# rs485.net
KiCad netlist of a schematic drawn in EAGLE
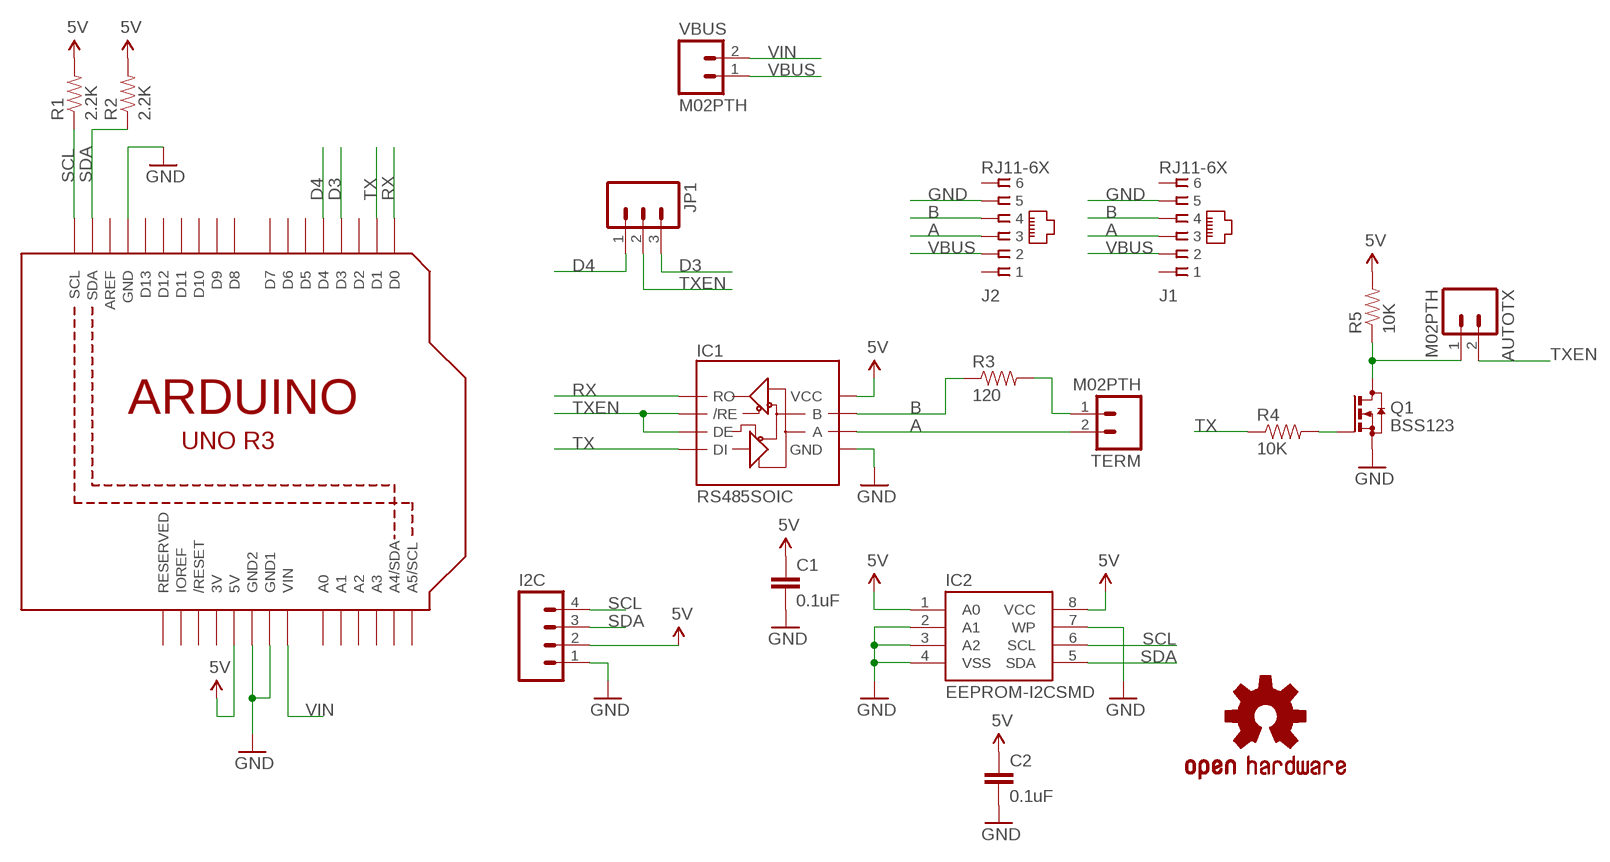
[diagram p0: schematic, sheet 1]

(export (version "E")
  (design (tool "Eeschema 10.0.6"))
  (components
    (comp (ref "AUTOTX")
      (value "M02PTH")
      (footprint "eagle-import:1X02")
      (libsource (lib "eagle-import") (part "M02PTH"))
    )
    (comp (ref "C1")
      (value "0.1uF")
      (footprint "eagle-import:0603-CAP")
      (libsource (lib "eagle-import") (part "CAP0603-CAP"))
    )
    (comp (ref "C2")
      (value "0.1uF")
      (footprint "eagle-import:0603-CAP")
      (libsource (lib "eagle-import") (part "CAP0603-CAP"))
    )
    (comp (ref "I2C")
      (value "M04PTH")
      (footprint "eagle-import:1X04")
      (libsource (lib "eagle-import") (part "M04PTH"))
    )
    (comp (ref "IC1")
      (value "RS485SOIC")
      (footprint "eagle-import:SO08")
      (libsource (lib "eagle-import") (part "RS485SOIC"))
    )
    (comp (ref "IC2")
      (value "EEPROM-I2CSMD")
      (footprint "eagle-import:SO08")
      (libsource (lib "eagle-import") (part "EEPROM-I2CSMD"))
    )
    (comp (ref "J1")
      (value "RJ11-6X")
      (footprint "eagle-import:RJ11-NO_SHIELD")
      (libsource (lib "eagle-import") (part "RJ11-6X"))
    )
    (comp (ref "J2")
      (value "RJ11-6X")
      (footprint "eagle-import:RJ11-NO_SHIELD")
      (libsource (lib "eagle-import") (part "RJ11-6X"))
    )
    (comp (ref "JP1")
      (value "M03PTH")
      (footprint "eagle-import:1X03")
      (libsource (lib "eagle-import") (part "M03PTH"))
    )
    (comp (ref "LOGO1")
      (value "OSHW-LOGOL")
      (footprint "eagle-import:OSHW-LOGO-L")
      (libsource (lib "eagle-import") (part "OSHW-LOGOL"))
    )
    (comp (ref "Q1")
      (value "BSS123")
      (footprint "eagle-import:SOT23")
      (libsource (lib "eagle-import") (part "BSS123"))
    )
    (comp (ref "R1")
      (value "2.2K")
      (footprint "eagle-import:0603-RES")
      (libsource (lib "eagle-import") (part "RESISTOR0603-RES"))
    )
    (comp (ref "R2")
      (value "2.2K")
      (footprint "eagle-import:0603-RES")
      (libsource (lib "eagle-import") (part "RESISTOR0603-RES"))
    )
    (comp (ref "R3")
      (value "120")
      (footprint "eagle-import:0603-RES")
      (libsource (lib "eagle-import") (part "RESISTOR0603-RES"))
    )
    (comp (ref "R4")
      (value "10K")
      (footprint "eagle-import:0603-RES")
      (libsource (lib "eagle-import") (part "RESISTOR0603-RES"))
    )
    (comp (ref "R5")
      (value "10K")
      (footprint "eagle-import:0603-RES")
      (libsource (lib "eagle-import") (part "RESISTOR0603-RES"))
    )
    (comp (ref "TERM")
      (value "M02PTH")
      (footprint "eagle-import:1X02")
      (libsource (lib "eagle-import") (part "M02PTH"))
    )
    (comp (ref "U1")
      (value "ARDUINOR3-JUSTPINS")
      (footprint "eagle-import:ARDUINOR3")
      (libsource (lib "eagle-import") (part "ARDUINOR3-JUSTPINS"))
    )
    (comp (ref "VBUS")
      (value "M02PTH")
      (footprint "eagle-import:1X02")
      (libsource (lib "eagle-import") (part "M02PTH"))
    )
  )
  (nets
    (net (code "1") (name "/3V") (class "Default")
      (node (ref "U1") (pin "3V") (pinfunction "3V_3V") (pintype "power_in"))
    )
    (net (code "2") (name "/A") (class "Default")
      (node (ref "IC1") (pin "6") (pinfunction "A_6") (pintype "bidirectional"))
      (node (ref "J1") (pin "3") (pinfunction "3_3") (pintype "passive"))
      (node (ref "J2") (pin "3") (pinfunction "3_3") (pintype "passive"))
      (node (ref "TERM") (pin "2") (pinfunction "2_2") (pintype "passive"))
    )
    (net (code "3") (name "/B") (class "Default")
      (node (ref "IC1") (pin "7") (pinfunction "B_7") (pintype "bidirectional"))
      (node (ref "J1") (pin "4") (pinfunction "4_4") (pintype "passive"))
      (node (ref "J2") (pin "4") (pinfunction "4_4") (pintype "passive"))
      (node (ref "R3") (pin "1") (pinfunction "1_1") (pintype "passive"))
    )
    (net (code "4") (name "/D3") (class "Default")
      (node (ref "JP1") (pin "3") (pinfunction "3_3") (pintype "passive"))
      (node (ref "U1") (pin "D3") (pinfunction "D3_D3") (pintype "bidirectional"))
    )
    (net (code "5") (name "/D4") (class "Default")
      (node (ref "JP1") (pin "1") (pinfunction "1_1") (pintype "passive"))
      (node (ref "U1") (pin "D4") (pinfunction "D4_D4") (pintype "bidirectional"))
    )
    (net (code "6") (name "/RX") (class "Default")
      (node (ref "IC1") (pin "1") (pinfunction "RO_1") (pintype "bidirectional"))
      (node (ref "U1") (pin "D0") (pinfunction "D0_D0") (pintype "bidirectional"))
    )
    (net (code "7") (name "/SCL") (class "Default")
      (node (ref "I2C") (pin "4") (pinfunction "4_4") (pintype "passive"))
      (node (ref "IC2") (pin "6") (pinfunction "SCL_6") (pintype "bidirectional"))
      (node (ref "R1") (pin "1") (pinfunction "1_1") (pintype "passive"))
      (node (ref "U1") (pin "SCL") (pinfunction "SCL_SCL") (pintype "bidirectional"))
    )
    (net (code "8") (name "/SDA") (class "Default")
      (node (ref "I2C") (pin "3") (pinfunction "3_3") (pintype "passive"))
      (node (ref "IC2") (pin "5") (pinfunction "SDA_5") (pintype "bidirectional"))
      (node (ref "R2") (pin "1") (pinfunction "1_1") (pintype "passive"))
      (node (ref "U1") (pin "SDA") (pinfunction "SDA_SDA") (pintype "bidirectional"))
    )
    (net (code "9") (name "/TX") (class "Default")
      (node (ref "IC1") (pin "4") (pinfunction "DI_4") (pintype "bidirectional"))
      (node (ref "R4") (pin "1") (pinfunction "1_1") (pintype "passive"))
      (node (ref "U1") (pin "D1") (pinfunction "D1_D1") (pintype "bidirectional"))
    )
    (net (code "10") (name "/TXEN") (class "Default")
      (node (ref "AUTOTX") (pin "2") (pinfunction "2_2") (pintype "passive"))
      (node (ref "IC1") (pin "2") (pinfunction "/RE_2") (pintype "bidirectional"))
      (node (ref "IC1") (pin "3") (pinfunction "DE_3") (pintype "bidirectional"))
      (node (ref "JP1") (pin "2") (pinfunction "2_2") (pintype "passive"))
    )
    (net (code "11") (name "/VBUS") (class "Default")
      (node (ref "J1") (pin "2") (pinfunction "2_2") (pintype "passive"))
      (node (ref "J2") (pin "2") (pinfunction "2_2") (pintype "passive"))
      (node (ref "VBUS") (pin "1") (pinfunction "1_1") (pintype "passive"))
    )
    (net (code "12") (name "/VIN") (class "Default")
      (node (ref "U1") (pin "VIN") (pinfunction "VIN_VIN") (pintype "power_in"))
      (node (ref "VBUS") (pin "2") (pinfunction "2_2") (pintype "passive"))
    )
    (net (code "13") (name "5V") (class "Default")
      (node (ref "C1") (pin "1") (pinfunction "1_1") (pintype "passive"))
      (node (ref "C2") (pin "1") (pinfunction "1_1") (pintype "passive"))
      (node (ref "I2C") (pin "2") (pinfunction "2_2") (pintype "passive"))
      (node (ref "IC1") (pin "8") (pinfunction "VCC_8") (pintype "bidirectional"))
      (node (ref "IC2") (pin "1") (pinfunction "A0_1") (pintype "bidirectional"))
      (node (ref "IC2") (pin "8") (pinfunction "VCC_8") (pintype "power_in"))
      (node (ref "R1") (pin "2") (pinfunction "2_2") (pintype "passive"))
      (node (ref "R2") (pin "2") (pinfunction "2_2") (pintype "passive"))
      (node (ref "R5") (pin "2") (pinfunction "2_2") (pintype "passive"))
      (node (ref "U1") (pin "5V") (pinfunction "5V_5V") (pintype "power_in"))
    )
    (net (code "14") (name "GND") (class "Default")
      (node (ref "C1") (pin "2") (pinfunction "2_2") (pintype "passive"))
      (node (ref "C2") (pin "2") (pinfunction "2_2") (pintype "passive"))
      (node (ref "I2C") (pin "1") (pinfunction "1_1") (pintype "passive"))
      (node (ref "IC1") (pin "5") (pinfunction "GND_5") (pintype "bidirectional"))
      (node (ref "IC2") (pin "2") (pinfunction "A1_2") (pintype "bidirectional"))
      (node (ref "IC2") (pin "3") (pinfunction "A2_3") (pintype "bidirectional"))
      (node (ref "IC2") (pin "4") (pinfunction "VSS_4") (pintype "power_in"))
      (node (ref "IC2") (pin "7") (pinfunction "WP_7") (pintype "bidirectional"))
      (node (ref "J1") (pin "5") (pinfunction "5_5") (pintype "passive"))
      (node (ref "J2") (pin "5") (pinfunction "5_5") (pintype "passive"))
      (node (ref "Q1") (pin "2") (pinfunction "S_2") (pintype "passive"))
      (node (ref "U1") (pin "GND") (pinfunction "GND_GND") (pintype "power_in"))
      (node (ref "U1") (pin "GND1") (pinfunction "GND1_GND1") (pintype "power_in"))
      (node (ref "U1") (pin "GND2") (pinfunction "GND2_GND2") (pintype "power_in"))
    )
    (net (code "15") (name "Net-(Q1-D)") (class "Default")
      (node (ref "AUTOTX") (pin "1") (pinfunction "1_1") (pintype "passive"))
      (node (ref "Q1") (pin "3") (pinfunction "D_3") (pintype "passive"))
      (node (ref "R5") (pin "1") (pinfunction "1_1") (pintype "passive"))
    )
    (net (code "16") (name "Net-(Q1-G)") (class "Default")
      (node (ref "Q1") (pin "1") (pinfunction "G_1") (pintype "passive"))
      (node (ref "R4") (pin "2") (pinfunction "2_2") (pintype "passive"))
    )
    (net (code "17") (name "Net-(R3-Pad2)") (class "Default")
      (node (ref "R3") (pin "2") (pinfunction "2_2") (pintype "passive"))
      (node (ref "TERM") (pin "1") (pinfunction "1_1") (pintype "passive"))
    )
    (net (code "18") (name "unconnected-(J1-Pad1)") (class "Default")
      (node (ref "J1") (pin "1") (pinfunction "1_1") (pintype "passive"))
    )
    (net (code "19") (name "unconnected-(J1-Pad6)") (class "Default")
      (node (ref "J1") (pin "6") (pinfunction "6_6") (pintype "passive"))
    )
    (net (code "20") (name "unconnected-(J2-Pad1)") (class "Default")
      (node (ref "J2") (pin "1") (pinfunction "1_1") (pintype "passive"))
    )
    (net (code "21") (name "unconnected-(J2-Pad6)") (class "Default")
      (node (ref "J2") (pin "6") (pinfunction "6_6") (pintype "passive"))
    )
    (net (code "22") (name "unconnected-(U1-A4{slash}SDA-PadA4)") (class "Default")
      (node (ref "U1") (pin "A4") (pinfunction "A4/SDA_A4") (pintype "bidirectional"))
    )
    (net (code "23") (name "unconnected-(U1-A5{slash}SCL-PadA5)") (class "Default")
      (node (ref "U1") (pin "A5") (pinfunction "A5/SCL_A5") (pintype "bidirectional"))
    )
    (net (code "24") (name "unconnected-(U1-PadA0)") (class "Default")
      (node (ref "U1") (pin "A0") (pinfunction "A0_A0") (pintype "bidirectional"))
    )
    (net (code "25") (name "unconnected-(U1-PadA1)") (class "Default")
      (node (ref "U1") (pin "A1") (pinfunction "A1_A1") (pintype "bidirectional"))
    )
    (net (code "26") (name "unconnected-(U1-PadA2)") (class "Default")
      (node (ref "U1") (pin "A2") (pinfunction "A2_A2") (pintype "bidirectional"))
    )
    (net (code "27") (name "unconnected-(U1-PadA3)") (class "Default")
      (node (ref "U1") (pin "A3") (pinfunction "A3_A3") (pintype "bidirectional"))
    )
    (net (code "28") (name "unconnected-(U1-PadAREF)") (class "Default")
      (node (ref "U1") (pin "AREF") (pinfunction "AREF_AREF") (pintype "bidirectional"))
    )
    (net (code "29") (name "unconnected-(U1-PadD2)") (class "Default")
      (node (ref "U1") (pin "D2") (pinfunction "D2_D2") (pintype "bidirectional"))
    )
    (net (code "30") (name "unconnected-(U1-PadD5)") (class "Default")
      (node (ref "U1") (pin "D5") (pinfunction "D5_D5") (pintype "bidirectional"))
    )
    (net (code "31") (name "unconnected-(U1-PadD6)") (class "Default")
      (node (ref "U1") (pin "D6") (pinfunction "D6_D6") (pintype "bidirectional"))
    )
    (net (code "32") (name "unconnected-(U1-PadD7)") (class "Default")
      (node (ref "U1") (pin "D7") (pinfunction "D7_D7") (pintype "bidirectional"))
    )
    (net (code "33") (name "unconnected-(U1-PadD8)") (class "Default")
      (node (ref "U1") (pin "D8") (pinfunction "D8_D8") (pintype "bidirectional"))
    )
    (net (code "34") (name "unconnected-(U1-PadD9)") (class "Default")
      (node (ref "U1") (pin "D9") (pinfunction "D9_D9") (pintype "bidirectional"))
    )
    (net (code "35") (name "unconnected-(U1-PadD10)") (class "Default")
      (node (ref "U1") (pin "D10") (pinfunction "D10_D10") (pintype "bidirectional"))
    )
    (net (code "36") (name "unconnected-(U1-PadD11)") (class "Default")
      (node (ref "U1") (pin "D11") (pinfunction "D11_D11") (pintype "bidirectional"))
    )
    (net (code "37") (name "unconnected-(U1-PadD12)") (class "Default")
      (node (ref "U1") (pin "D12") (pinfunction "D12_D12") (pintype "bidirectional"))
    )
    (net (code "38") (name "unconnected-(U1-PadD13)") (class "Default")
      (node (ref "U1") (pin "D13") (pinfunction "D13_D13") (pintype "bidirectional"))
    )
    (net (code "39") (name "unconnected-(U1-PadIOREF)") (class "Default")
      (node (ref "U1") (pin "IOREF") (pinfunction "IOREF_IOREF") (pintype "output"))
    )
    (net (code "40") (name "unconnected-(U1-PadRESERVED)") (class "Default")
      (node (ref "U1") (pin "RESERVED") (pinfunction "RESERVED_RESERVED") (pintype "no_connect"))
    )
    (net (code "41") (name "unconnected-(U1-{slash}RESET-PadRESET)") (class "Default")
      (node (ref "U1") (pin "RESET") (pinfunction "/RESET_RESET") (pintype "bidirectional"))
    )
  )
)
